# Window_comparator.net
KiCad netlist of a schematic drawn in Altium Designer
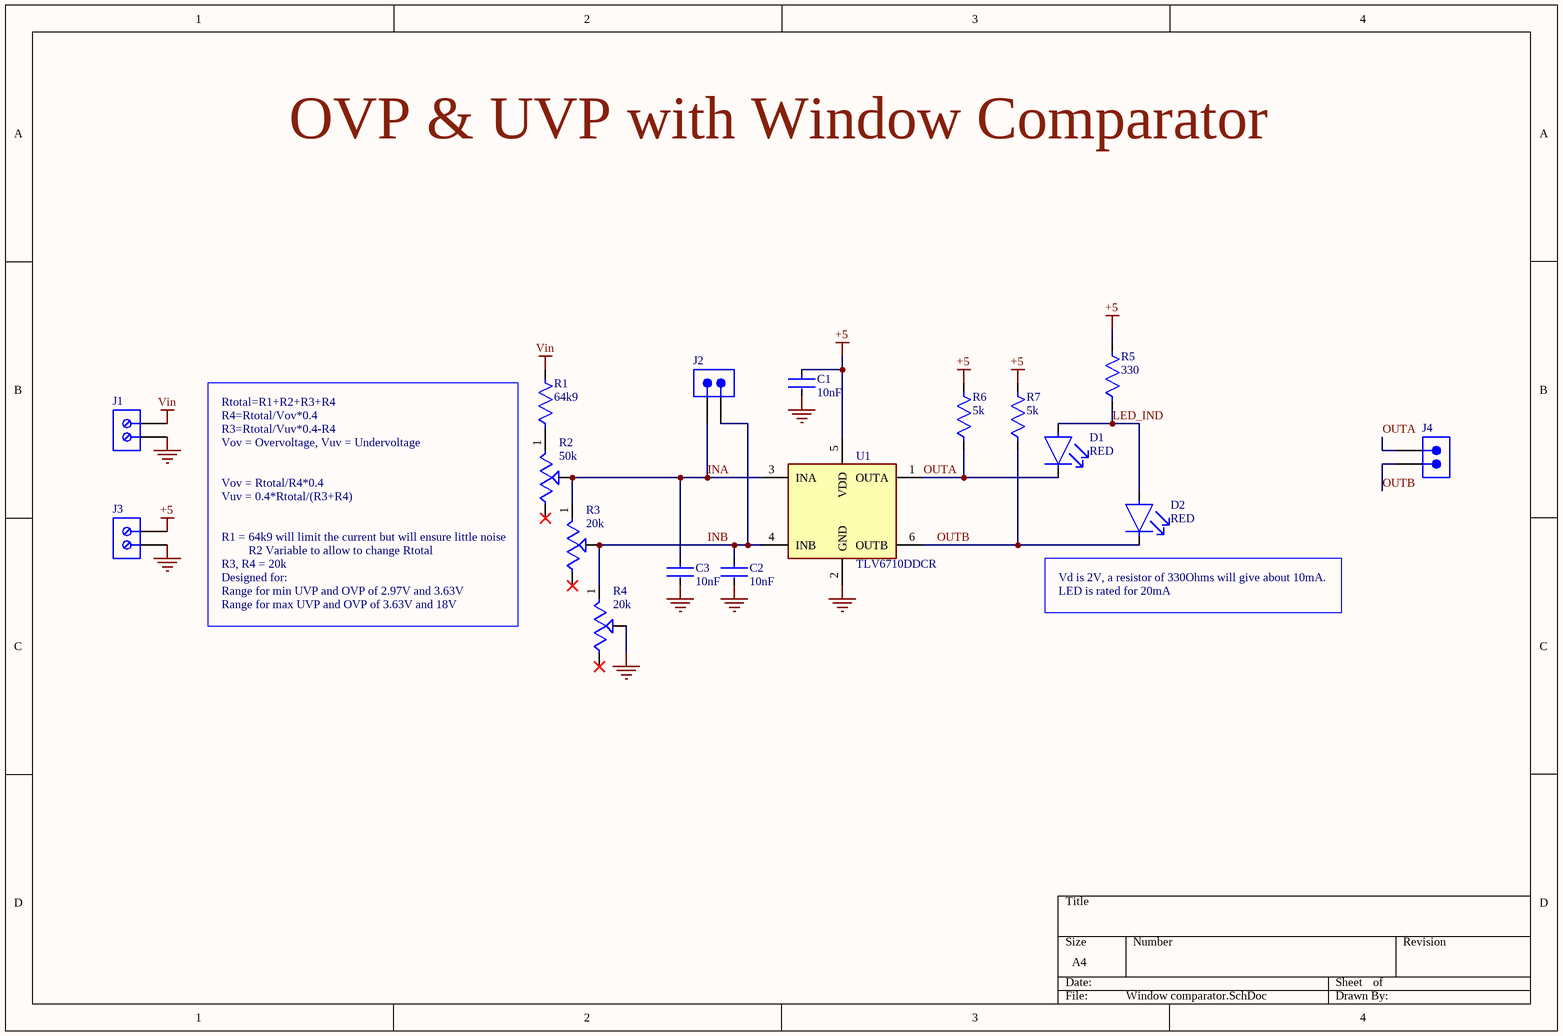
[diagram p0: Window comparator.SchDoc]

(export (version "E")
  (design (tool "Eeschema 10.0.6"))
  (components
    (comp (ref "C1")
      (value "10nF")
      (footprint "C0805")
      (fields
        (field (name "MANUFACTURER") "KEMET")
        (field (name "MANUFACTURER PART NUMBER") "C0805C103K5RECAUTO")
      )
      (libsource (lib "Window Comparator Lib") (part "C0805C103K5RECAUTO"))
    )
    (comp (ref "C2")
      (value "10nF")
      (footprint "C0805")
      (fields
        (field (name "MANUFACTURER") "KEMET")
        (field (name "MANUFACTURER PART NUMBER") "C0805C103K5RECAUTO")
      )
      (libsource (lib "Window Comparator Lib") (part "C0805C103K5RECAUTO"))
    )
    (comp (ref "C3")
      (value "10nF")
      (footprint "C0805")
      (fields
        (field (name "MANUFACTURER") "KEMET")
        (field (name "MANUFACTURER PART NUMBER") "C0805C103K5RECAUTO")
      )
      (libsource (lib "Window Comparator Lib") (part "C0805C103K5RECAUTO"))
    )
    (comp (ref "D1")
      (value "RED")
      (footprint "LED RED")
      (description "Single Color LED, Super Red, 1.1mm")
      (fields
        (field (name "MANUFACTURER") "Vishay Semiconductors")
        (field (name "MANUFACTURER PART NUMBER") "VLMS1300-GS08")
      )
      (libsource (lib "Window Comparator Lib") (part "VLMS1300-GS08"))
    )
    (comp (ref "D2")
      (value "RED")
      (footprint "LED RED")
      (description "Single Color LED, Super Red, 1.1mm")
      (fields
        (field (name "MANUFACTURER") "Vishay Semiconductors")
        (field (name "MANUFACTURER PART NUMBER") "VLMS1300-GS08")
      )
      (libsource (lib "Window Comparator Lib") (part "VLMS1300-GS08"))
    )
    (comp (ref "J1")
      (value "691137710002")
      (footprint "Wire terminal")
      (description "Barrier Strip Terminal Block")
      (fields (field (name "MANUFACTURER") "Wurth Electronics"))
      (libsource (lib "Window Comparator Lib") (part "691137710002"))
    )
    (comp (ref "J2")
      (value "61300211121")
      (footprint "Pin connector")
      (fields (field (name "MANUFACTURER") "Wurth Electronics"))
      (libsource (lib "Window Comparator Lib") (part "61300211121"))
    )
    (comp (ref "J3")
      (value "691137710002")
      (footprint "Wire terminal")
      (description "Barrier Strip Terminal Block")
      (fields (field (name "MANUFACTURER") "Wurth Electronics"))
      (libsource (lib "Window Comparator Lib") (part "691137710002"))
    )
    (comp (ref "J4")
      (value "61300211121")
      (footprint "Pin connector")
      (fields (field (name "MANUFACTURER") "Wurth Electronics"))
      (libsource (lib "Window Comparator Lib") (part "61300211121"))
    )
    (comp (ref "R1")
      (value "64k9")
      (footprint "R0805")
      (fields
        (field (name "MANUFACTURER") "Vishay")
        (field (name "MANUFACTURER PART NUMBER") "CRCW080564K9FKEA")
        (field (name "TOLERANCE") "1%")
      )
      (libsource (lib "Window Comparator Lib") (part "CRCW080564K9FKEA"))
    )
    (comp (ref "R2")
      (value "50k")
      (footprint "TS63Y Trimmer")
      (description "Trimmer, Cermet, 0.25W, 50000ohm, 112V, 10% +/-Tol, 100ppm/Cel, 14 Turn(s), 2720")
      (fields
        (field (name "MANUFACTURER") "Vishay Sfernice")
        (field (name "MANUFACTURER PART NUMBER") "TS63Y503KR10")
      )
      (libsource (lib "Window Comparator Lib") (part "TS63Y503KR10"))
    )
    (comp (ref "R3")
      (value "20k")
      (footprint "TS63Y Trimmer")
      (description "Trimmer, Cermet, 0.25W, 20000ohm, 70.7V, 10% +/-Tol, 100ppm/Cel, 14 Turn(s), 2720")
      (fields
        (field (name "MANUFACTURER") "Vishay Sfernice")
        (field (name "MANUFACTURER PART NUMBER") "TS63Y203KR10")
      )
      (libsource (lib "Window Comparator Lib") (part "TS63Y203KR10"))
    )
    (comp (ref "R4")
      (value "20k")
      (footprint "TS63Y Trimmer")
      (description "Trimmer, Cermet, 0.25W, 20000ohm, 70.7V, 10% +/-Tol, 100ppm/Cel, 14 Turn(s), 2720")
      (fields
        (field (name "MANUFACTURER") "Vishay Sfernice")
        (field (name "MANUFACTURER PART NUMBER") "TS63Y203KR10")
      )
      (libsource (lib "Window Comparator Lib") (part "TS63Y203KR10"))
    )
    (comp (ref "R5")
      (value "330")
      (footprint "R0805")
      (fields
        (field (name "MANUFACTURER") "Vishay")
        (field (name "MANUFACTURER PART NUMBER") "CRCW0805330RJNEAC")
        (field (name "TOLERANCE") "5%")
      )
      (libsource (lib "Window Comparator Lib") (part "CRCW0805330RJNEAC"))
    )
    (comp (ref "R6")
      (value "5k")
      (footprint "R0805")
      (description "SMD Chip Resistor, 5 kOhm, ± 5%, 125 mW, 0805 [2012 Metric], Thick Film, General Purpose")
      (fields
        (field (name "MANUFACTURER") "Vishay")
        (field (name "MANUFACTURER PART NUMBER") "CRCW08055K00JNTA")
      )
      (libsource (lib "Window Comparator Lib") (part "CRCW08055K00JNTA"))
    )
    (comp (ref "R7")
      (value "5k")
      (footprint "R0805")
      (description "SMD Chip Resistor, 5 kOhm, ± 5%, 125 mW, 0805 [2012 Metric], Thick Film, General Purpose")
      (fields
        (field (name "MANUFACTURER") "Vishay")
        (field (name "MANUFACTURER PART NUMBER") "CRCW08055K00JNTA")
      )
      (libsource (lib "Window Comparator Lib") (part "CRCW08055K00JNTA"))
    )
    (comp (ref "U1")
      (value "TLV6710DDCR")
      (footprint "TLV6710DDCR")
      (description "Comparator, 2 Func, 2000uV Offset-Max, 28100ns Response Time, PDSO6")
      (fields (field (name "MANUFACTURER") "Texas Instruments"))
      (libsource (lib "Window Comparator Lib") (part "TLV6710DDCR"))
    )
  )
  (nets
    (net (code "1") (name "+5") (class "Default")
      (node (ref "C1") (pin "1") (pinfunction "1_1") (pintype "passive"))
      (node (ref "J3") (pin "2") (pinfunction "2_2") (pintype "passive"))
      (node (ref "R5") (pin "2") (pinfunction "2_2") (pintype "passive"))
      (node (ref "R6") (pin "2") (pinfunction "2_2") (pintype "passive"))
      (node (ref "R7") (pin "2") (pinfunction "2_2") (pintype "passive"))
      (node (ref "U1") (pin "5") (pinfunction "VDD_5") (pintype "power_in"))
    )
    (net (code "2") (name "/INA") (class "Default")
      (node (ref "C3") (pin "1") (pinfunction "1_1") (pintype "passive"))
      (node (ref "J2") (pin "1") (pinfunction "1_1") (pintype "passive"))
      (node (ref "R2") (pin "2") (pinfunction "B_2") (pintype "passive"))
      (node (ref "R3") (pin "1") (pinfunction "A_1") (pintype "passive"))
      (node (ref "U1") (pin "3") (pinfunction "INA_3") (pintype "tri_state"))
    )
    (net (code "3") (name "/INB") (class "Default")
      (node (ref "C2") (pin "1") (pinfunction "1_1") (pintype "passive"))
      (node (ref "J2") (pin "2") (pinfunction "2_2") (pintype "passive"))
      (node (ref "R3") (pin "2") (pinfunction "B_2") (pintype "passive"))
      (node (ref "R4") (pin "1") (pinfunction "A_1") (pintype "passive"))
      (node (ref "U1") (pin "4") (pinfunction "INB_4") (pintype "tri_state"))
    )
    (net (code "4") (name "/LED_IND") (class "Default")
      (node (ref "D1") (pin "2") (pinfunction "A_2") (pintype "passive"))
      (node (ref "D2") (pin "2") (pinfunction "A_2") (pintype "passive"))
      (node (ref "R5") (pin "1") (pinfunction "1_1") (pintype "passive"))
    )
    (net (code "5") (name "/OUTA") (class "Default")
      (node (ref "D1") (pin "1") (pinfunction "C_1") (pintype "passive"))
      (node (ref "J4") (pin "1") (pinfunction "1_1") (pintype "passive"))
      (node (ref "R6") (pin "1") (pinfunction "1_1") (pintype "passive"))
      (node (ref "U1") (pin "1") (pinfunction "OUTA_1") (pintype "passive"))
    )
    (net (code "6") (name "/OUTB") (class "Default")
      (node (ref "D2") (pin "1") (pinfunction "C_1") (pintype "passive"))
      (node (ref "J4") (pin "2") (pinfunction "2_2") (pintype "passive"))
      (node (ref "R7") (pin "1") (pinfunction "1_1") (pintype "passive"))
      (node (ref "U1") (pin "6") (pinfunction "OUTB_6") (pintype "passive"))
    )
    (net (code "7") (name "GND") (class "Default")
      (node (ref "C1") (pin "2") (pinfunction "2_2") (pintype "passive"))
      (node (ref "C2") (pin "2") (pinfunction "2_2") (pintype "passive"))
      (node (ref "C3") (pin "2") (pinfunction "2_2") (pintype "passive"))
      (node (ref "J1") (pin "1") (pinfunction "1_1") (pintype "passive"))
      (node (ref "J3") (pin "1") (pinfunction "1_1") (pintype "passive"))
      (node (ref "R4") (pin "2") (pinfunction "B_2") (pintype "passive"))
      (node (ref "U1") (pin "2") (pinfunction "GND_2") (pintype "power_in"))
    )
    (net (code "8") (name "Net-(R2-A)") (class "Default")
      (node (ref "R1") (pin "1") (pinfunction "1_1") (pintype "passive"))
      (node (ref "R2") (pin "1") (pinfunction "A_1") (pintype "passive"))
    )
    (net (code "9") (name "Vin") (class "Default")
      (node (ref "J1") (pin "2") (pinfunction "2_2") (pintype "passive"))
      (node (ref "R1") (pin "2") (pinfunction "2_2") (pintype "passive"))
    )
    (net (code "10") (name "unconnected-(R2-C-Pad3)") (class "Default")
      (node (ref "R2") (pin "3") (pinfunction "C_3") (pintype "passive+no_connect"))
    )
    (net (code "11") (name "unconnected-(R3-C-Pad3)") (class "Default")
      (node (ref "R3") (pin "3") (pinfunction "C_3") (pintype "passive+no_connect"))
    )
    (net (code "12") (name "unconnected-(R4-C-Pad3)") (class "Default")
      (node (ref "R4") (pin "3") (pinfunction "C_3") (pintype "passive+no_connect"))
    )
  )
)
